# tgam_breakout.net
KiCad netlist of a schematic drawn in EAGLE
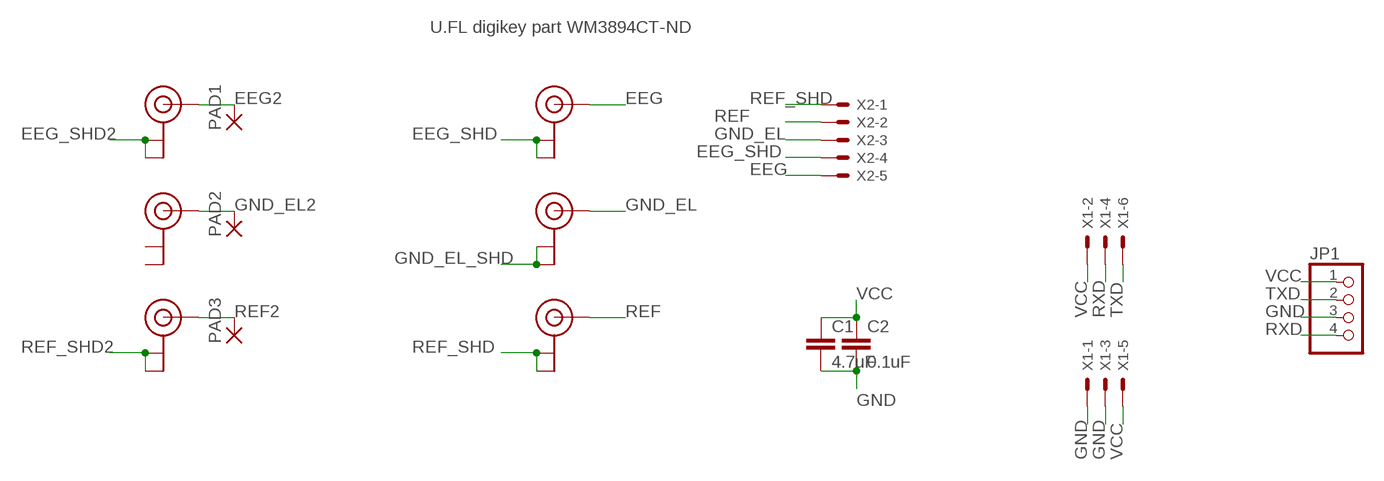
[diagram p0: schematic, sheet 1]

(export (version "E")
  (design (tool "Eeschema 10.0.6"))
  (components
    (comp (ref "C1")
      (value "4.7uF")
      (footprint "eagle-import:C0805")
      (libsource (lib "eagle-import") (part "C-EUC0805"))
    )
    (comp (ref "C2")
      (value "0.1uF")
      (footprint "eagle-import:C0805")
      (libsource (lib "eagle-import") (part "C-EUC0805"))
    )
    (comp (ref "EEG")
      (value "U.FL")
      (footprint "eagle-import:U.FL")
      (libsource (lib "eagle-import") (part "U.FL"))
    )
    (comp (ref "EEG_EL")
      (value "U.FL")
      (footprint "eagle-import:U.FL")
      (libsource (lib "eagle-import") (part "U.FL"))
    )
    (comp (ref "GND_EL")
      (value "U.FL")
      (footprint "eagle-import:U.FL")
      (libsource (lib "eagle-import") (part "U.FL"))
    )
    (comp (ref "GND_ELEL")
      (value "U.FL")
      (footprint "eagle-import:U.FL")
      (libsource (lib "eagle-import") (part "U.FL"))
    )
    (comp (ref "JP1")
      (value "PINHD-1X4")
      (footprint "eagle-import:1X04")
      (libsource (lib "eagle-import") (part "PINHD-1X4"))
    )
    (comp (ref "PAD1")
      (value "SMD5")
      (footprint "eagle-import:SMD2,54-5,08")
      (libsource (lib "eagle-import") (part "SMD5"))
    )
    (comp (ref "PAD2")
      (value "SMD5")
      (footprint "eagle-import:SMD2,54-5,08")
      (libsource (lib "eagle-import") (part "SMD5"))
    )
    (comp (ref "PAD3")
      (value "SMD5")
      (footprint "eagle-import:SMD2,54-5,08")
      (libsource (lib "eagle-import") (part "SMD5"))
    )
    (comp (ref "REF")
      (value "U.FL")
      (footprint "eagle-import:U.FL")
      (libsource (lib "eagle-import") (part "U.FL"))
    )
    (comp (ref "REF_EL")
      (value "U.FL")
      (footprint "eagle-import:U.FL")
      (libsource (lib "eagle-import") (part "U.FL"))
    )
    (comp (ref "X1")
      (value "332-06")
      (footprint "eagle-import:332-06")
      (libsource (lib "eagle-import") (part "332-06"))
    )
    (comp (ref "X2")
      (value "332-10")
      (footprint "eagle-import:2MM5SIL")
      (libsource (lib "eagle-import") (part "332-10"))
    )
  )
  (nets
    (net (code "1") (name "/EEG") (class "Default")
      (node (ref "EEG") (pin "P$3") (pinfunction "SIGNAL_P$3") (pintype "bidirectional"))
      (node (ref "X2") (pin "9") (pinfunction "S_9") (pintype "passive"))
    )
    (net (code "2") (name "/EEG2") (class "Default")
      (node (ref "EEG_EL") (pin "P$3") (pinfunction "SIGNAL_P$3") (pintype "bidirectional"))
      (node (ref "PAD1") (pin "1") (pinfunction "P_1") (pintype "passive"))
    )
    (net (code "3") (name "/EEG_SHD") (class "Default")
      (node (ref "EEG") (pin "P$1") (pinfunction "GND_P$1") (pintype "bidirectional"))
      (node (ref "EEG") (pin "P$2") (pinfunction "GND_P$2") (pintype "bidirectional"))
      (node (ref "X2") (pin "7") (pinfunction "S_7") (pintype "passive"))
    )
    (net (code "4") (name "/EEG_SHD2") (class "Default")
      (node (ref "EEG_EL") (pin "P$1") (pinfunction "GND_P$1") (pintype "bidirectional"))
      (node (ref "EEG_EL") (pin "P$2") (pinfunction "GND_P$2") (pintype "bidirectional"))
    )
    (net (code "5") (name "/GND") (class "Default")
      (node (ref "C1") (pin "2") (pinfunction "2_2") (pintype "passive"))
      (node (ref "C2") (pin "2") (pinfunction "2_2") (pintype "passive"))
      (node (ref "JP1") (pin "3") (pinfunction "3_3") (pintype "passive"))
      (node (ref "X1") (pin "1") (pinfunction "S_1") (pintype "passive"))
      (node (ref "X1") (pin "3") (pinfunction "S_3") (pintype "passive"))
    )
    (net (code "6") (name "/GND_EL") (class "Default")
      (node (ref "GND_EL") (pin "P$3") (pinfunction "SIGNAL_P$3") (pintype "bidirectional"))
      (node (ref "X2") (pin "5") (pinfunction "S_5") (pintype "passive"))
    )
    (net (code "7") (name "/GND_EL2") (class "Default")
      (node (ref "GND_ELEL") (pin "P$3") (pinfunction "SIGNAL_P$3") (pintype "bidirectional"))
      (node (ref "PAD2") (pin "1") (pinfunction "P_1") (pintype "passive"))
    )
    (net (code "8") (name "/GND_EL_SHD") (class "Default")
      (node (ref "GND_EL") (pin "P$1") (pinfunction "GND_P$1") (pintype "bidirectional"))
      (node (ref "GND_EL") (pin "P$2") (pinfunction "GND_P$2") (pintype "bidirectional"))
    )
    (net (code "9") (name "/REF") (class "Default")
      (node (ref "REF") (pin "P$3") (pinfunction "SIGNAL_P$3") (pintype "bidirectional"))
      (node (ref "X2") (pin "3") (pinfunction "S_3") (pintype "passive"))
    )
    (net (code "10") (name "/REF2") (class "Default")
      (node (ref "PAD3") (pin "1") (pinfunction "P_1") (pintype "passive"))
      (node (ref "REF_EL") (pin "P$3") (pinfunction "SIGNAL_P$3") (pintype "bidirectional"))
    )
    (net (code "11") (name "/REF_SHD") (class "Default")
      (node (ref "REF") (pin "P$1") (pinfunction "GND_P$1") (pintype "bidirectional"))
      (node (ref "REF") (pin "P$2") (pinfunction "GND_P$2") (pintype "bidirectional"))
      (node (ref "X2") (pin "1") (pinfunction "S_1") (pintype "passive"))
    )
    (net (code "12") (name "/REF_SHD2") (class "Default")
      (node (ref "REF_EL") (pin "P$1") (pinfunction "GND_P$1") (pintype "bidirectional"))
      (node (ref "REF_EL") (pin "P$2") (pinfunction "GND_P$2") (pintype "bidirectional"))
    )
    (net (code "13") (name "/RXD") (class "Default")
      (node (ref "JP1") (pin "4") (pinfunction "4_4") (pintype "passive"))
      (node (ref "X1") (pin "4") (pinfunction "S_4") (pintype "passive"))
    )
    (net (code "14") (name "/TXD") (class "Default")
      (node (ref "JP1") (pin "2") (pinfunction "2_2") (pintype "passive"))
      (node (ref "X1") (pin "6") (pinfunction "S_6") (pintype "passive"))
    )
    (net (code "15") (name "/VCC") (class "Default")
      (node (ref "C1") (pin "1") (pinfunction "1_1") (pintype "passive"))
      (node (ref "C2") (pin "1") (pinfunction "1_1") (pintype "passive"))
      (node (ref "JP1") (pin "1") (pinfunction "1_1") (pintype "passive"))
      (node (ref "X1") (pin "2") (pinfunction "S_2") (pintype "passive"))
      (node (ref "X1") (pin "5") (pinfunction "S_5") (pintype "passive"))
    )
    (net (code "16") (name "unconnected-(GND_ELEL-GND-PadP$1)") (class "Default")
      (node (ref "GND_ELEL") (pin "P$1") (pinfunction "GND_P$1") (pintype "bidirectional"))
    )
    (net (code "17") (name "unconnected-(GND_ELEL-GND-PadP$2)") (class "Default")
      (node (ref "GND_ELEL") (pin "P$2") (pinfunction "GND_P$2") (pintype "bidirectional"))
    )
  )
)
